# LiDAR_Demo_Board.net
KiCad netlist of a schematic drawn in EAGLE
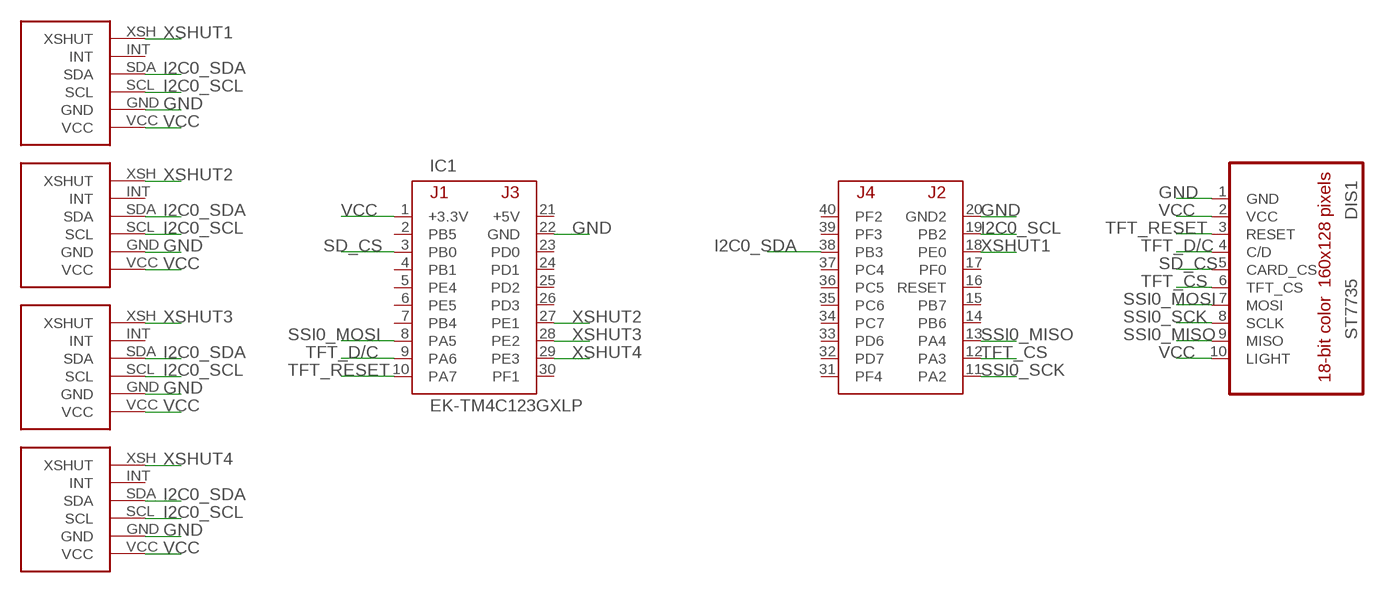
[diagram p0: schematic, sheet 1]

(export (version "E")
  (design (tool "Eeschema 10.0.6"))
  (components
    (comp (ref "DIS1")
      (value "ST7735")
      (footprint "eagle-import:ST7735")
      (libsource (lib "eagle-import") (part "ST7735"))
    )
    (comp (ref "IC1")
      (value "EK-TM4C123GXLP")
      (footprint "eagle-import:TM4C123LAUNCHPAD")
      (libsource (lib "eagle-import") (part "EK-TM4C123GXLP"))
    )
    (comp (ref "U$1")
      (value "VL53L0X_ATK")
      (footprint "eagle-import:VL53L0X_ATK")
      (libsource (lib "eagle-import") (part "VL53L0X_ATK"))
    )
    (comp (ref "U$2")
      (value "VL53L0X_ATK")
      (footprint "eagle-import:VL53L0X_ATK")
      (libsource (lib "eagle-import") (part "VL53L0X_ATK"))
    )
    (comp (ref "U$3")
      (value "VL53L0X_ATK")
      (footprint "eagle-import:VL53L0X_ATK")
      (libsource (lib "eagle-import") (part "VL53L0X_ATK"))
    )
    (comp (ref "U$4")
      (value "VL53L0X_ATK")
      (footprint "eagle-import:VL53L0X_ATK")
      (libsource (lib "eagle-import") (part "VL53L0X_ATK"))
    )
  )
  (nets
    (net (code "1") (name "/+5V") (class "Default")
      (node (ref "IC1") (pin "21") (pinfunction "+5V_21") (pintype "power_in"))
    )
    (net (code "2") (name "/GND") (class "Default")
      (node (ref "DIS1") (pin "1") (pinfunction "GND_1") (pintype "power_in"))
      (node (ref "IC1") (pin "20") (pinfunction "GND2_20") (pintype "power_in"))
      (node (ref "IC1") (pin "22") (pinfunction "GND_22") (pintype "power_in"))
      (node (ref "U$1") (pin "GND") (pinfunction "GND_GND") (pintype "bidirectional"))
      (node (ref "U$2") (pin "GND") (pinfunction "GND_GND") (pintype "bidirectional"))
      (node (ref "U$3") (pin "GND") (pinfunction "GND_GND") (pintype "bidirectional"))
      (node (ref "U$4") (pin "GND") (pinfunction "GND_GND") (pintype "bidirectional"))
    )
    (net (code "3") (name "/I2C0_SCL") (class "Default")
      (node (ref "IC1") (pin "19") (pinfunction "PB2_19") (pintype "bidirectional"))
      (node (ref "U$1") (pin "SCL") (pinfunction "SCL_SCL") (pintype "bidirectional"))
      (node (ref "U$2") (pin "SCL") (pinfunction "SCL_SCL") (pintype "bidirectional"))
      (node (ref "U$3") (pin "SCL") (pinfunction "SCL_SCL") (pintype "bidirectional"))
      (node (ref "U$4") (pin "SCL") (pinfunction "SCL_SCL") (pintype "bidirectional"))
    )
    (net (code "4") (name "/I2C0_SDA") (class "Default")
      (node (ref "IC1") (pin "38") (pinfunction "PB3_38") (pintype "bidirectional"))
      (node (ref "U$1") (pin "SDA") (pinfunction "SDA_SDA") (pintype "bidirectional"))
      (node (ref "U$2") (pin "SDA") (pinfunction "SDA_SDA") (pintype "bidirectional"))
      (node (ref "U$3") (pin "SDA") (pinfunction "SDA_SDA") (pintype "bidirectional"))
      (node (ref "U$4") (pin "SDA") (pinfunction "SDA_SDA") (pintype "bidirectional"))
    )
    (net (code "5") (name "/SD_CS") (class "Default")
      (node (ref "DIS1") (pin "5") (pinfunction "CARD_CS_5") (pintype "input"))
      (node (ref "IC1") (pin "3") (pinfunction "PB0_3") (pintype "bidirectional"))
    )
    (net (code "6") (name "/SSI0_MISO") (class "Default")
      (node (ref "DIS1") (pin "9") (pinfunction "MISO_9") (pintype "output"))
      (node (ref "IC1") (pin "13") (pinfunction "PA4_13") (pintype "bidirectional"))
    )
    (net (code "7") (name "/SSI0_MOSI") (class "Default")
      (node (ref "DIS1") (pin "7") (pinfunction "MOSI_7") (pintype "input"))
      (node (ref "IC1") (pin "8") (pinfunction "PA5_8") (pintype "bidirectional"))
    )
    (net (code "8") (name "/SSI0_SCK") (class "Default")
      (node (ref "DIS1") (pin "8") (pinfunction "SCLK_8") (pintype "input"))
      (node (ref "IC1") (pin "11") (pinfunction "PA2_11") (pintype "bidirectional"))
    )
    (net (code "9") (name "/TFT_CS") (class "Default")
      (node (ref "DIS1") (pin "6") (pinfunction "TFT_CS_6") (pintype "input"))
      (node (ref "IC1") (pin "12") (pinfunction "PA3_12") (pintype "bidirectional"))
    )
    (net (code "10") (name "/TFT_D{slash}C") (class "Default")
      (node (ref "DIS1") (pin "4") (pinfunction "C/D_4") (pintype "input"))
      (node (ref "IC1") (pin "9") (pinfunction "PA6_9") (pintype "bidirectional"))
    )
    (net (code "11") (name "/TFT_RESET") (class "Default")
      (node (ref "DIS1") (pin "3") (pinfunction "RESET_3") (pintype "input"))
      (node (ref "IC1") (pin "10") (pinfunction "PA7_10") (pintype "bidirectional"))
    )
    (net (code "12") (name "/VCC") (class "Default")
      (node (ref "DIS1") (pin "10") (pinfunction "LIGHT_10") (pintype "passive"))
      (node (ref "DIS1") (pin "2") (pinfunction "VCC_2") (pintype "power_in"))
      (node (ref "IC1") (pin "1") (pinfunction "+3.3V_1") (pintype "power_in"))
      (node (ref "U$1") (pin "VCC") (pinfunction "VCC_VCC") (pintype "bidirectional"))
      (node (ref "U$2") (pin "VCC") (pinfunction "VCC_VCC") (pintype "bidirectional"))
      (node (ref "U$3") (pin "VCC") (pinfunction "VCC_VCC") (pintype "bidirectional"))
      (node (ref "U$4") (pin "VCC") (pinfunction "VCC_VCC") (pintype "bidirectional"))
    )
    (net (code "13") (name "/XSHUT1") (class "Default")
      (node (ref "IC1") (pin "18") (pinfunction "PE0_18") (pintype "bidirectional"))
      (node (ref "U$1") (pin "XSH") (pinfunction "XSHUT_XSH") (pintype "bidirectional"))
    )
    (net (code "14") (name "/XSHUT2") (class "Default")
      (node (ref "IC1") (pin "27") (pinfunction "PE1_27") (pintype "bidirectional"))
      (node (ref "U$2") (pin "XSH") (pinfunction "XSHUT_XSH") (pintype "bidirectional"))
    )
    (net (code "15") (name "/XSHUT3") (class "Default")
      (node (ref "IC1") (pin "28") (pinfunction "PE2_28") (pintype "bidirectional"))
      (node (ref "U$3") (pin "XSH") (pinfunction "XSHUT_XSH") (pintype "bidirectional"))
    )
    (net (code "16") (name "/XSHUT4") (class "Default")
      (node (ref "IC1") (pin "29") (pinfunction "PE3_29") (pintype "bidirectional"))
      (node (ref "U$4") (pin "XSH") (pinfunction "XSHUT_XSH") (pintype "bidirectional"))
    )
    (net (code "17") (name "unconnected-(IC1-PB1-Pad4)") (class "Default")
      (node (ref "IC1") (pin "4") (pinfunction "PB1_4") (pintype "bidirectional"))
    )
    (net (code "18") (name "unconnected-(IC1-PB4-Pad7)") (class "Default")
      (node (ref "IC1") (pin "7") (pinfunction "PB4_7") (pintype "bidirectional"))
    )
    (net (code "19") (name "unconnected-(IC1-PB5-Pad2)") (class "Default")
      (node (ref "IC1") (pin "2") (pinfunction "PB5_2") (pintype "bidirectional"))
    )
    (net (code "20") (name "unconnected-(IC1-PB6-Pad14)") (class "Default")
      (node (ref "IC1") (pin "14") (pinfunction "PB6_14") (pintype "bidirectional"))
    )
    (net (code "21") (name "unconnected-(IC1-PB7-Pad15)") (class "Default")
      (node (ref "IC1") (pin "15") (pinfunction "PB7_15") (pintype "bidirectional"))
    )
    (net (code "22") (name "unconnected-(IC1-PC4-Pad37)") (class "Default")
      (node (ref "IC1") (pin "37") (pinfunction "PC4_37") (pintype "bidirectional"))
    )
    (net (code "23") (name "unconnected-(IC1-PC5-Pad36)") (class "Default")
      (node (ref "IC1") (pin "36") (pinfunction "PC5_36") (pintype "bidirectional"))
    )
    (net (code "24") (name "unconnected-(IC1-PC6-Pad35)") (class "Default")
      (node (ref "IC1") (pin "35") (pinfunction "PC6_35") (pintype "bidirectional"))
    )
    (net (code "25") (name "unconnected-(IC1-PC7-Pad34)") (class "Default")
      (node (ref "IC1") (pin "34") (pinfunction "PC7_34") (pintype "bidirectional"))
    )
    (net (code "26") (name "unconnected-(IC1-PD0-Pad23)") (class "Default")
      (node (ref "IC1") (pin "23") (pinfunction "PD0_23") (pintype "bidirectional"))
    )
    (net (code "27") (name "unconnected-(IC1-PD1-Pad24)") (class "Default")
      (node (ref "IC1") (pin "24") (pinfunction "PD1_24") (pintype "bidirectional"))
    )
    (net (code "28") (name "unconnected-(IC1-PD2-Pad25)") (class "Default")
      (node (ref "IC1") (pin "25") (pinfunction "PD2_25") (pintype "bidirectional"))
    )
    (net (code "29") (name "unconnected-(IC1-PD3-Pad26)") (class "Default")
      (node (ref "IC1") (pin "26") (pinfunction "PD3_26") (pintype "bidirectional"))
    )
    (net (code "30") (name "unconnected-(IC1-PD6-Pad33)") (class "Default")
      (node (ref "IC1") (pin "33") (pinfunction "PD6_33") (pintype "bidirectional"))
    )
    (net (code "31") (name "unconnected-(IC1-PD7-Pad32)") (class "Default")
      (node (ref "IC1") (pin "32") (pinfunction "PD7_32") (pintype "bidirectional"))
    )
    (net (code "32") (name "unconnected-(IC1-PE4-Pad5)") (class "Default")
      (node (ref "IC1") (pin "5") (pinfunction "PE4_5") (pintype "bidirectional"))
    )
    (net (code "33") (name "unconnected-(IC1-PE5-Pad6)") (class "Default")
      (node (ref "IC1") (pin "6") (pinfunction "PE5_6") (pintype "bidirectional"))
    )
    (net (code "34") (name "unconnected-(IC1-PF0-Pad17)") (class "Default")
      (node (ref "IC1") (pin "17") (pinfunction "PF0_17") (pintype "bidirectional"))
    )
    (net (code "35") (name "unconnected-(IC1-PF1-Pad30)") (class "Default")
      (node (ref "IC1") (pin "30") (pinfunction "PF1_30") (pintype "bidirectional"))
    )
    (net (code "36") (name "unconnected-(IC1-PF2-Pad40)") (class "Default")
      (node (ref "IC1") (pin "40") (pinfunction "PF2_40") (pintype "bidirectional"))
    )
    (net (code "37") (name "unconnected-(IC1-PF3-Pad39)") (class "Default")
      (node (ref "IC1") (pin "39") (pinfunction "PF3_39") (pintype "bidirectional"))
    )
    (net (code "38") (name "unconnected-(IC1-PF4-Pad31)") (class "Default")
      (node (ref "IC1") (pin "31") (pinfunction "PF4_31") (pintype "bidirectional"))
    )
    (net (code "39") (name "unconnected-(IC1-RESET-Pad16)") (class "Default")
      (node (ref "IC1") (pin "16") (pinfunction "RESET_16") (pintype "input"))
    )
    (net (code "40") (name "unconnected-(U$1-PadINT)") (class "Default")
      (node (ref "U$1") (pin "INT") (pinfunction "INT_INT") (pintype "bidirectional"))
    )
    (net (code "41") (name "unconnected-(U$2-PadINT)") (class "Default")
      (node (ref "U$2") (pin "INT") (pinfunction "INT_INT") (pintype "bidirectional"))
    )
    (net (code "42") (name "unconnected-(U$3-PadINT)") (class "Default")
      (node (ref "U$3") (pin "INT") (pinfunction "INT_INT") (pintype "bidirectional"))
    )
    (net (code "43") (name "unconnected-(U$4-PadINT)") (class "Default")
      (node (ref "U$4") (pin "INT") (pinfunction "INT_INT") (pintype "bidirectional"))
    )
  )
)
